# 06_ACCELEROMETER.net
KiCad netlist of a schematic drawn in Altium Designer
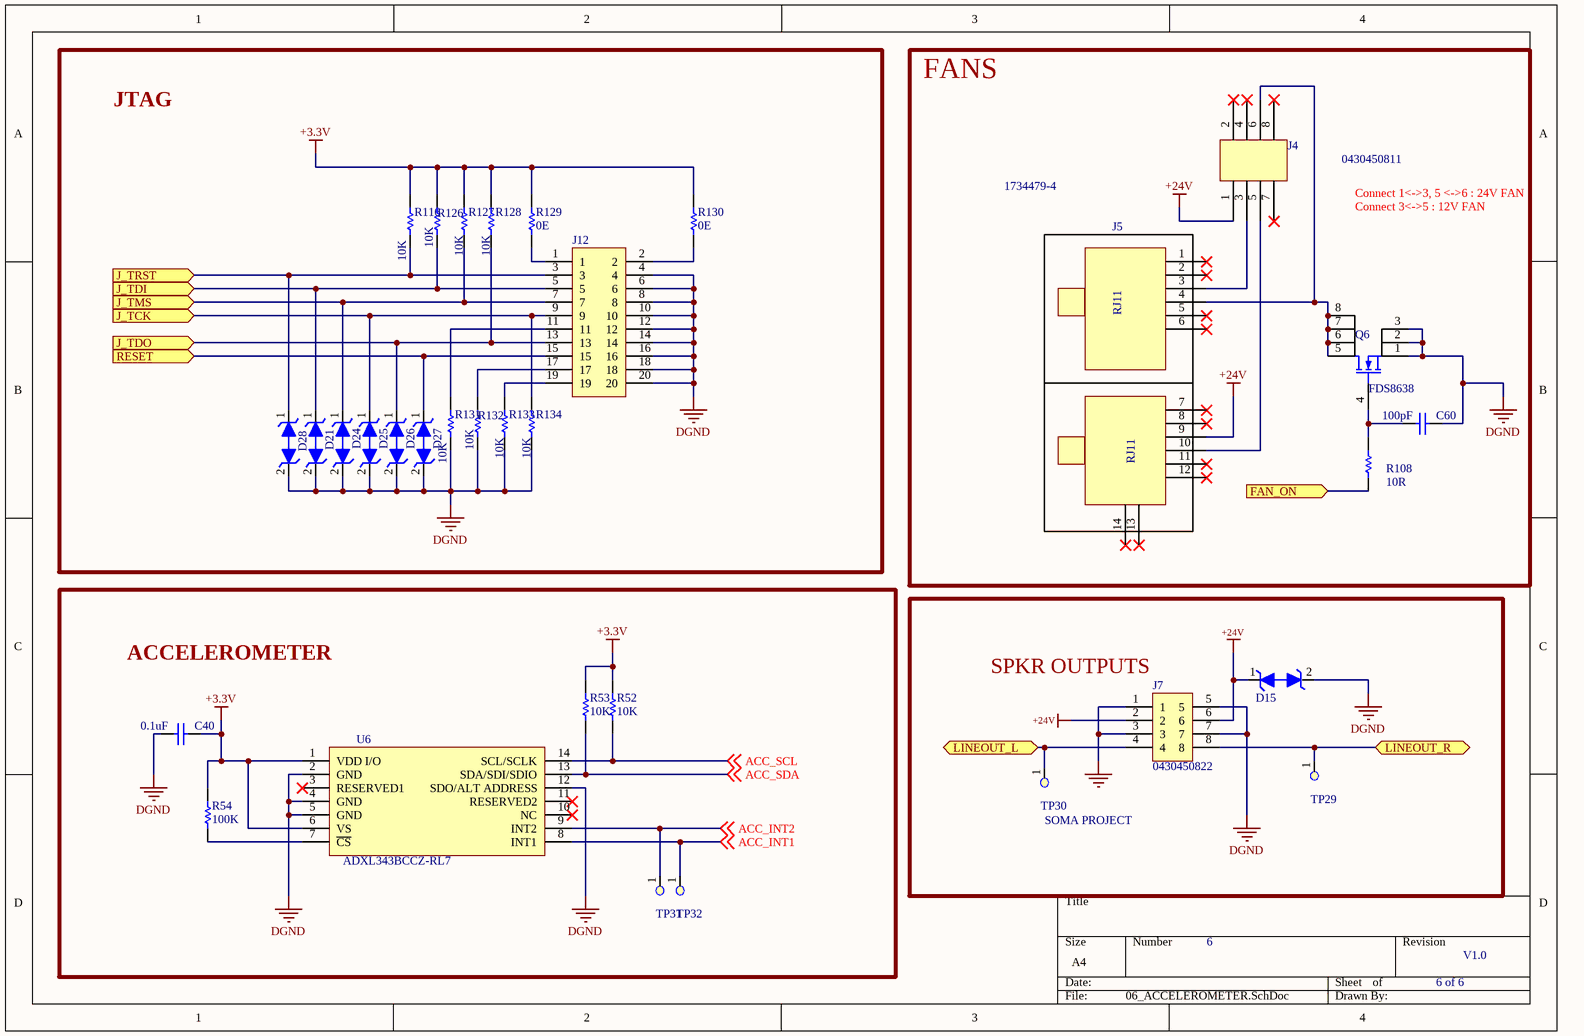
[diagram p0: 06_ACCELEROMETER.SchDoc]

(export (version "E")
  (design (tool "Eeschema 10.0.6"))
  (components
    (comp (ref "C40")
      (value "0.1uF")
      (footprint "C0402")
      (description "CAP CER 0.1UF 50V X7R 0402")
      (fields
        (field (name "MANUFACTURER") "AVX Corporation")
        (field (name "MANUFACTURER PART NUMBER") "04025C104KAT2A")
      )
      (libsource (lib "SOMA_15072021") (part "CAP CER 0.1UF 50V X7R 0402_1"))
    )
    (comp (ref "C60")
      (value "100pF")
      (footprint "C0402")
      (description "100 pF ±5% 50V Ceramic Capacitor C0G, NP0 0402 (1005 Metric)")
      (fields (field (name "TOLERANCE") "±5%") (field (name "MANUFACTURER") "KEMET"))
      (libsource (lib "SOMA_15072021") (part "CAP CER 100PF 50V C0G/NP0 0402"))
    )
    (comp (ref "D15")
      (value "TVS DIODE 24VWM 38.9VC SMC")
      (footprint "SOD8060X260N_BI")
      (description "38.9V Clamp 77.2A Ipp Tvs Diode Surface Mount DO-214AB (SMC)")
      (fields
        (field (name "MANUFACTURER") "Bourns Inc.")
        (field (name "MANUFACTURER PART NUMBER") "SMLJ24CA-Q")
      )
      (libsource (lib "SOMA_1") (part "TVS DIODE 24VWM 38.9VC SMC"))
    )
    (comp (ref "D21")
      (value "TVS DIODE 3.3V 11.5V SOD923")
      (footprint "SOD1006X40N_BI")
      (fields
        (field (name "MANUFACTURER PART NUMBER") "ESD9B3.3ST5G")
        (field (name "MANUFACTURER") "ON Semiconductor")
        (field (name "DISTRIBUTOR PART NUMBER") "ESD9B3.3ST5GOSTR-ND")
      )
      (libsource (lib "Daughtercard_Library") (part "Diode,ESD9B3.3ST5G"))
    )
    (comp (ref "D24")
      (value "TVS DIODE 3.3V 11.5V SOD923")
      (footprint "SOD1006X40N_BI")
      (fields
        (field (name "MANUFACTURER PART NUMBER") "ESD9B3.3ST5G")
        (field (name "MANUFACTURER") "ON Semiconductor")
        (field (name "DISTRIBUTOR PART NUMBER") "ESD9B3.3ST5GOSTR-ND")
      )
      (libsource (lib "Daughtercard_Library") (part "Diode,ESD9B3.3ST5G"))
    )
    (comp (ref "D25")
      (value "TVS DIODE 3.3V 11.5V SOD923")
      (footprint "SOD1006X40N_BI")
      (fields
        (field (name "MANUFACTURER PART NUMBER") "ESD9B3.3ST5G")
        (field (name "MANUFACTURER") "ON Semiconductor")
        (field (name "DISTRIBUTOR PART NUMBER") "ESD9B3.3ST5GOSTR-ND")
      )
      (libsource (lib "Daughtercard_Library") (part "Diode,ESD9B3.3ST5G"))
    )
    (comp (ref "D26")
      (value "TVS DIODE 3.3V 11.5V SOD923")
      (footprint "SOD1006X40N_BI")
      (fields
        (field (name "MANUFACTURER PART NUMBER") "ESD9B3.3ST5G")
        (field (name "MANUFACTURER") "ON Semiconductor")
        (field (name "DISTRIBUTOR PART NUMBER") "ESD9B3.3ST5GOSTR-ND")
      )
      (libsource (lib "Daughtercard_Library") (part "Diode,ESD9B3.3ST5G"))
    )
    (comp (ref "D27")
      (value "TVS DIODE 3.3V 11.5V SOD923")
      (footprint "SOD1006X40N_BI")
      (fields
        (field (name "MANUFACTURER PART NUMBER") "ESD9B3.3ST5G")
        (field (name "MANUFACTURER") "ON Semiconductor")
        (field (name "DISTRIBUTOR PART NUMBER") "ESD9B3.3ST5GOSTR-ND")
      )
      (libsource (lib "Daughtercard_Library") (part "Diode,ESD9B3.3ST5G"))
    )
    (comp (ref "D28")
      (value "TVS DIODE 3.3V 11.5V SOD923")
      (footprint "SOD1006X40N_BI")
      (fields
        (field (name "MANUFACTURER PART NUMBER") "ESD9B3.3ST5G")
        (field (name "MANUFACTURER") "ON Semiconductor")
        (field (name "DISTRIBUTOR PART NUMBER") "ESD9B3.3ST5GOSTR-ND")
      )
      (libsource (lib "Daughtercard_Library") (part "Diode,ESD9B3.3ST5G"))
    )
    (comp (ref "J4")
      (value "0430450811")
      (footprint "MOLEX_0430450811")
      (description "Connector Header Surface Mount, Right Angle 8 position 0.118\" (3.00mm)")
      (fields (field (name "DISTRIBUTOR PART NUMBER") "WM1834CT-ND") (field (name "MANUFACTURER") "Molex"))
      (libsource (lib "SOMA_15072021") (part "CONN HEADER SMD R/A 8POS 3MM"))
    )
    (comp (ref "J5")
      (value "1734479-4")
      (footprint "TE_17344794")
      (description "Jack Modular Connector 6p4c (RJ11, RJ14) 90° Angle (Right) Unshielded Cat3")
      (fields
        (field (name "DISTRIBUTOR PART NUMBER") "A119279-ND")
        (field (name "MANUFACTURER") "TE Connectivity AMP Connectors")
      )
      (libsource (lib "SOMA_15072021") (part "CONN MOD JACK 6P4C R/A UNSHLD"))
    )
    (comp (ref "J7")
      (value "0430450822")
      (footprint "MOLEX_430450822")
      (description "Connector Header Through Hole, Right Angle 8 position 0.118\" (3.00mm)")
      (fields (field (name "MANUFACTURER") "Molex") (field (name "DISTRIBUTOR PART NUMBER") "WM2681-ND"))
      (libsource (lib "SOMA_15072021") (part "CONN HEADER R/A 8POS 3MM"))
    )
    (comp (ref "J12")
      (value "SBH11-NBPC-D10-SM-BK")
      (footprint "SULLINS_SBH11-NBPC-D10-SM-BK")
      (fields
        (field (name "DISTRIBUTOR PART NUMBER") "S9188-ND")
        (field (name "MANUFACTURER") "Sullins")
        (field (name "TOLERANCE") "NA")
      )
      (libsource (lib "SOMA_15072021") (part "SBH11-NBPC-D10-SM-BK"))
    )
    (comp (ref "Q6")
      (value "FDS8638")
      (footprint "SOIC127P600X175-8N")
      (description "N-Channel 40 V 18A (Ta) 2.5W (Ta) Surface Mount 8-SOIC")
      (fields
        (field (name "DISTRIBUTOR PART NUMBER") "FDS8638CT-ND")
        (field (name "MANUFACTURER") "ON Semiconductor")
      )
      (libsource (lib "SOMA_15072021") (part "MOSFET N-CH 40V 18A 8SOIC"))
    )
    (comp (ref "R52")
      (value "10K")
      (footprint "R0402")
      (description "10 kOhms ±1% 0.1W, 1/10W Chip Resistor 0402 (1005 Metric) Automotive AEC-Q200 Thick Film")
      (fields
        (field (name "MANUFACTURER") "Panasonic Electronic Components")
        (field (name "DISTRIBUTOR PART NUMBER") "P10.0KLCT-ND")
      )
      (libsource (lib "Daughtercard_Library") (part "RES SMD 10K OHM 1% 1/10W 0402"))
    )
    (comp (ref "R53")
      (value "10K")
      (footprint "R0402")
      (description "10 kOhms ±1% 0.1W, 1/10W Chip Resistor 0402 (1005 Metric) Automotive AEC-Q200 Thick Film")
      (fields
        (field (name "MANUFACTURER") "Panasonic Electronic Components")
        (field (name "DISTRIBUTOR PART NUMBER") "P10.0KLCT-ND")
      )
      (libsource (lib "Daughtercard_Library") (part "RES SMD 10K OHM 1% 1/10W 0402"))
    )
    (comp (ref "R54")
      (value "100K")
      (footprint "R0402")
      (description "100 kOhms ±1% 0.1W, 1/10W Chip Resistor 0402 (1005 Metric) Automotive AEC-Q200 Thick Film")
      (fields
        (field (name "MANUFACTURER") "Panasonic Electronic Components")
        (field (name "MANUFACTURER PART NUMBER") "ERJ-2RKF1003X")
      )
      (libsource (lib "SOMA_15072021") (part "RES SMD 100K OHM 1% 1/10W 0402"))
    )
    (comp (ref "R108")
      (value "10R")
      (footprint "R0402")
      (description "10 Ohms ±5% 0.063W, 1/16W Chip Resistor 0402 (1005 Metric) Automotive AEC-Q200 Thick Film")
      (fields (field (name "TOLERANCE") "±5%") (field (name "MANUFACTURER") "Vishay Dale"))
      (libsource (lib "SOMA_15072021") (part "RES SMD 10 OHM 5% 1/16W 0402"))
    )
    (comp (ref "R116")
      (value "10K")
      (footprint "R0402")
      (description "10 kOhms ±1% 0.1W, 1/10W Chip Resistor 0402 (1005 Metric) Automotive AEC-Q200 Thick Film")
      (fields
        (field (name "MANUFACTURER") "Panasonic Electronic Components")
        (field (name "DISTRIBUTOR PART NUMBER") "P10.0KLCT-ND")
      )
      (libsource (lib "Daughtercard_Library") (part "RES SMD 10K OHM 1% 1/10W 0402"))
    )
    (comp (ref "R126")
      (value "10K")
      (footprint "R0402")
      (description "10 kOhms ±1% 0.1W, 1/10W Chip Resistor 0402 (1005 Metric) Automotive AEC-Q200 Thick Film")
      (fields
        (field (name "MANUFACTURER") "Panasonic Electronic Components")
        (field (name "DISTRIBUTOR PART NUMBER") "P10.0KLCT-ND")
      )
      (libsource (lib "Daughtercard_Library") (part "RES SMD 10K OHM 1% 1/10W 0402"))
    )
    (comp (ref "R127")
      (value "10K")
      (footprint "R0402")
      (description "10 kOhms ±1% 0.1W, 1/10W Chip Resistor 0402 (1005 Metric) Automotive AEC-Q200 Thick Film")
      (fields
        (field (name "MANUFACTURER") "Panasonic Electronic Components")
        (field (name "DISTRIBUTOR PART NUMBER") "P10.0KLCT-ND")
      )
      (libsource (lib "Daughtercard_Library") (part "RES SMD 10K OHM 1% 1/10W 0402"))
    )
    (comp (ref "R128")
      (value "10K")
      (footprint "R0402")
      (description "10 kOhms ±1% 0.1W, 1/10W Chip Resistor 0402 (1005 Metric) Automotive AEC-Q200 Thick Film")
      (fields
        (field (name "MANUFACTURER") "Panasonic Electronic Components")
        (field (name "DISTRIBUTOR PART NUMBER") "P10.0KLCT-ND")
      )
      (libsource (lib "Daughtercard_Library") (part "RES SMD 10K OHM 1% 1/10W 0402"))
    )
    (comp (ref "R129")
      (value "0E")
      (footprint "R0603")
      (description "RES SMD 0 OHM JUMPER 1/10W 0603")
      (fields
        (field (name "MANUFACTURER PART NUMBER") "RC0603JR-070RL")
        (field (name "MANUFACTURER") "Yageo")
      )
      (libsource (lib "PH_ORP_Sensor Board_Rev1") (part "RES SMD 0 OHM JUMPER 1/10W 0603"))
    )
    (comp (ref "R130")
      (value "0E")
      (footprint "R0603")
      (description "RES SMD 0 OHM JUMPER 1/10W 0603")
      (fields
        (field (name "MANUFACTURER PART NUMBER") "RC0603JR-070RL")
        (field (name "MANUFACTURER") "Yageo")
      )
      (libsource (lib "PH_ORP_Sensor Board_Rev1") (part "RES SMD 0 OHM JUMPER 1/10W 0603"))
    )
    (comp (ref "R131")
      (value "10K")
      (footprint "R0402")
      (description "10 kOhms ±1% 0.1W, 1/10W Chip Resistor 0402 (1005 Metric) Automotive AEC-Q200 Thick Film")
      (fields
        (field (name "MANUFACTURER") "Panasonic Electronic Components")
        (field (name "DISTRIBUTOR PART NUMBER") "P10.0KLCT-ND")
      )
      (libsource (lib "Daughtercard_Library") (part "RES SMD 10K OHM 1% 1/10W 0402"))
    )
    (comp (ref "R132")
      (value "10K")
      (footprint "R0402")
      (description "10 kOhms ±1% 0.1W, 1/10W Chip Resistor 0402 (1005 Metric) Automotive AEC-Q200 Thick Film")
      (fields
        (field (name "MANUFACTURER") "Panasonic Electronic Components")
        (field (name "DISTRIBUTOR PART NUMBER") "P10.0KLCT-ND")
      )
      (libsource (lib "Daughtercard_Library") (part "RES SMD 10K OHM 1% 1/10W 0402"))
    )
    (comp (ref "R133")
      (value "10K")
      (footprint "R0402")
      (description "10 kOhms ±1% 0.1W, 1/10W Chip Resistor 0402 (1005 Metric) Automotive AEC-Q200 Thick Film")
      (fields
        (field (name "MANUFACTURER") "Panasonic Electronic Components")
        (field (name "DISTRIBUTOR PART NUMBER") "P10.0KLCT-ND")
      )
      (libsource (lib "Daughtercard_Library") (part "RES SMD 10K OHM 1% 1/10W 0402"))
    )
    (comp (ref "R134")
      (value "10K")
      (footprint "R0402")
      (description "10 kOhms ±1% 0.1W, 1/10W Chip Resistor 0402 (1005 Metric) Automotive AEC-Q200 Thick Film")
      (fields
        (field (name "MANUFACTURER") "Panasonic Electronic Components")
        (field (name "DISTRIBUTOR PART NUMBER") "P10.0KLCT-ND")
      )
      (libsource (lib "Daughtercard_Library") (part "RES SMD 10K OHM 1% 1/10W 0402"))
    )
    (comp (ref "TP29")
      (value "Test Point,1.6mm Diameter,SMD")
      (footprint "TP_63C")
      (libsource (lib "SOMA_1") (part "Test Point,1.6mm Diameter,SMD"))
    )
    (comp (ref "TP30")
      (value "Test Point,1.6mm Diameter,SMD")
      (footprint "TP_63C")
      (libsource (lib "SOMA_1") (part "Test Point,1.6mm Diameter,SMD"))
    )
    (comp (ref "TP31")
      (value "Test Point,1.6mm Diameter,SMD")
      (footprint "TP_63C")
      (libsource (lib "SOMA_1") (part "Test Point,1.6mm Diameter,SMD"))
    )
    (comp (ref "TP32")
      (value "Test Point,1.6mm Diameter,SMD")
      (footprint "TP_63C")
      (libsource (lib "SOMA_1") (part "Test Point,1.6mm Diameter,SMD"))
    )
    (comp (ref "U6")
      (value "ACCEL 2-16G I2C/SPI 14LGA")
      (footprint "LGA14R80P8X6_500X300X100N")
      (description "Accelerometer X, Y, Z Axis ±2g, 4g, 8g, 16g 0.05Hz ~ 1.6kHz 14-LGA (3x5)")
      (fields
        (field (name "MANUFACTURER") "Analog Devices Inc.")
        (field (name "DISTRIBUTOR PART NUMBER") "ADXL343BCCZ-RL7CT-ND")
        (field (name "MANUFACTURER PART NUMBER") "ADXL343BCCZ-RL7")
      )
      (libsource (lib "SOMA_15072021") (part "ACCEL 2-16G I2C/SPI 14LGA"))
    )
  )
  (nets
    (net (code "1") (name "+3.3V") (class "Default")
      (node (ref "C40") (pin "1") (pinfunction "1_1") (pintype "passive"))
      (node (ref "R116") (pin "2") (pinfunction "2_2") (pintype "passive"))
      (node (ref "R126") (pin "2") (pinfunction "2_2") (pintype "passive"))
      (node (ref "R127") (pin "2") (pinfunction "2_2") (pintype "passive"))
      (node (ref "R128") (pin "2") (pinfunction "2_2") (pintype "passive"))
      (node (ref "R129") (pin "2") (pinfunction "2_2") (pintype "passive"))
      (node (ref "R130") (pin "2") (pinfunction "2_2") (pintype "passive"))
      (node (ref "R52") (pin "2") (pinfunction "2_2") (pintype "passive"))
      (node (ref "R53") (pin "2") (pinfunction "2_2") (pintype "passive"))
      (node (ref "R54") (pin "2") (pinfunction "2_2") (pintype "passive"))
      (node (ref "U6") (pin "1") (pinfunction "VDD_I/O_1") (pintype "passive"))
      (node (ref "U6") (pin "6") (pinfunction "VS_6") (pintype "passive"))
    )
    (net (code "2") (name "+24V") (class "Default")
      (node (ref "D15") (pin "1") (pinfunction "K_1") (pintype "passive"))
      (node (ref "J4") (pin "1") (pintype "passive"))
      (node (ref "J5") (pin "9") (pinfunction "9_9") (pintype "passive"))
      (node (ref "J7") (pin "2") (pinfunction "2_2") (pintype "passive"))
      (node (ref "J7") (pin "6") (pinfunction "6_6") (pintype "passive"))
    )
    (net (code "5") (name "/FAN_ON") (class "Default")
      (node (ref "R108") (pin "1") (pinfunction "1_1") (pintype "passive"))
    )
    (net (code "6") (name "/J_TCK") (class "Default")
      (node (ref "D25") (pin "1") (pinfunction "K_1") (pintype "passive"))
      (node (ref "J12") (pin "9") (pinfunction "9_9") (pintype "passive"))
      (node (ref "R134") (pin "2") (pinfunction "2_2") (pintype "passive"))
    )
    (net (code "7") (name "/J_TDI") (class "Default")
      (node (ref "D21") (pin "1") (pinfunction "K_1") (pintype "passive"))
      (node (ref "J12") (pin "5") (pinfunction "5_5") (pintype "passive"))
      (node (ref "R126") (pin "1") (pinfunction "1_1") (pintype "passive"))
    )
    (net (code "8") (name "/J_TDO") (class "Default")
      (node (ref "D26") (pin "1") (pinfunction "K_1") (pintype "passive"))
      (node (ref "J12") (pin "13") (pinfunction "13_13") (pintype "passive"))
      (node (ref "R128") (pin "1") (pinfunction "1_1") (pintype "passive"))
    )
    (net (code "9") (name "/J_TMS") (class "Default")
      (node (ref "D24") (pin "1") (pinfunction "K_1") (pintype "passive"))
      (node (ref "J12") (pin "7") (pinfunction "7_7") (pintype "passive"))
      (node (ref "R127") (pin "1") (pinfunction "1_1") (pintype "passive"))
    )
    (net (code "10") (name "/J_TRST") (class "Default")
      (node (ref "D28") (pin "1") (pinfunction "K_1") (pintype "passive"))
      (node (ref "J12") (pin "3") (pinfunction "3_3") (pintype "passive"))
      (node (ref "R116") (pin "1") (pinfunction "1_1") (pintype "passive"))
    )
    (net (code "11") (name "/LINEOUT_L") (class "Default")
      (node (ref "J7") (pin "4") (pinfunction "4_4") (pintype "passive"))
      (node (ref "TP30") (pin "1") (pinfunction "0_1") (pintype "passive"))
    )
    (net (code "12") (name "/LINEOUT_R") (class "Default")
      (node (ref "J7") (pin "8") (pinfunction "8_8") (pintype "passive"))
      (node (ref "TP29") (pin "1") (pinfunction "0_1") (pintype "passive"))
    )
    (net (code "13") (name "/RESET") (class "Default")
      (node (ref "D27") (pin "1") (pinfunction "K_1") (pintype "passive"))
      (node (ref "J12") (pin "15") (pinfunction "15_15") (pintype "passive"))
    )
    (net (code "14") (name "ACC_INT1") (class "Default")
      (node (ref "TP32") (pin "1") (pinfunction "0_1") (pintype "passive"))
      (node (ref "U6") (pin "8") (pinfunction "INT1_8") (pintype "passive"))
    )
    (net (code "15") (name "ACC_INT2") (class "Default")
      (node (ref "TP31") (pin "1") (pinfunction "0_1") (pintype "passive"))
      (node (ref "U6") (pin "9") (pinfunction "INT2_9") (pintype "passive"))
    )
    (net (code "16") (name "ACC_SCL") (class "Default")
      (node (ref "R52") (pin "1") (pinfunction "1_1") (pintype "passive"))
      (node (ref "U6") (pin "14") (pinfunction "SCL/SCLK_14") (pintype "passive"))
    )
    (net (code "17") (name "ACC_SDA") (class "Default")
      (node (ref "R53") (pin "1") (pinfunction "1_1") (pintype "passive"))
      (node (ref "U6") (pin "13") (pinfunction "SDA/SDI/SDIO_13") (pintype "passive"))
    )
    (net (code "18") (name "DGND") (class "Default")
      (node (ref "C40") (pin "2") (pinfunction "2_2") (pintype "passive"))
      (node (ref "C60") (pin "1") (pinfunction "1_1") (pintype "passive"))
      (node (ref "D15") (pin "2") (pinfunction "A_2") (pintype "passive"))
      (node (ref "D21") (pin "2") (pinfunction "A_2") (pintype "passive"))
      (node (ref "D24") (pin "2") (pinfunction "A_2") (pintype "passive"))
      (node (ref "D25") (pin "2") (pinfunction "A_2") (pintype "passive"))
      (node (ref "D26") (pin "2") (pinfunction "A_2") (pintype "passive"))
      (node (ref "D27") (pin "2") (pinfunction "A_2") (pintype "passive"))
      (node (ref "D28") (pin "2") (pinfunction "A_2") (pintype "passive"))
      (node (ref "J12") (pin "10") (pinfunction "10_10") (pintype "passive"))
      (node (ref "J12") (pin "12") (pinfunction "12_12") (pintype "passive"))
      (node (ref "J12") (pin "14") (pinfunction "14_14") (pintype "passive"))
      (node (ref "J12") (pin "16") (pinfunction "16_16") (pintype "passive"))
      (node (ref "J12") (pin "18") (pinfunction "18_18") (pintype "passive"))
      (node (ref "J12") (pin "20") (pinfunction "20_20") (pintype "passive"))
      (node (ref "J12") (pin "4") (pinfunction "4_4") (pintype "passive"))
      (node (ref "J12") (pin "6") (pinfunction "6_6") (pintype "passive"))
      (node (ref "J12") (pin "8") (pinfunction "8_8") (pintype "passive"))
      (node (ref "J7") (pin "5") (pinfunction "5_5") (pintype "passive"))
      (node (ref "J7") (pin "7") (pinfunction "7_7") (pintype "passive"))
      (node (ref "Q6") (pin "1") (pinfunction "1_1") (pintype "passive"))
      (node (ref "Q6") (pin "2") (pinfunction "2_2") (pintype "passive"))
      (node (ref "Q6") (pin "3") (pinfunction "3_3") (pintype "passive"))
      (node (ref "R131") (pin "1") (pinfunction "1_1") (pintype "passive"))
      (node (ref "R132") (pin "1") (pinfunction "1_1") (pintype "passive"))
      (node (ref "R133") (pin "1") (pinfunction "1_1") (pintype "passive"))
      (node (ref "R134") (pin "1") (pinfunction "1_1") (pintype "passive"))
      (node (ref "U6") (pin "12") (pinfunction "SDO/ALT_ADDRESS_12") (pintype "passive"))
      (node (ref "U6") (pin "2") (pinfunction "GND_2") (pintype "passive"))
      (node (ref "U6") (pin "4") (pinfunction "GND_4") (pintype "passive"))
      (node (ref "U6") (pin "5") (pinfunction "GND_5") (pintype "passive"))
    )
    (net (code "19") (name "GND") (class "Default")
      (node (ref "J7") (pin "1") (pinfunction "1_1") (pintype "passive"))
      (node (ref "J7") (pin "3") (pinfunction "3_3") (pintype "passive"))
    )
    (net (code "20") (name "Net-(C60-Pad2)") (class "Default")
      (node (ref "C60") (pin "2") (pinfunction "2_2") (pintype "passive"))
      (node (ref "Q6") (pin "4") (pinfunction "4_4") (pintype "passive"))
      (node (ref "R108") (pin "2") (pinfunction "2_2") (pintype "passive"))
    )
    (net (code "21") (name "Net-(J4-Pad3)") (class "Default")
      (node (ref "J4") (pin "3") (pintype "passive"))
      (node (ref "J5") (pin "3") (pinfunction "3_3") (pintype "passive"))
    )
    (net (code "22") (name "Net-(J4-Pad5)") (class "Default")
      (node (ref "J4") (pin "5") (pintype "passive"))
      (node (ref "J5") (pin "10") (pinfunction "10_10") (pintype "passive"))
    )
    (net (code "23") (name "Net-(J4-Pad6)") (class "Default")
      (node (ref "J4") (pin "6") (pintype "passive"))
      (node (ref "J5") (pin "4") (pinfunction "4_4") (pintype "passive"))
      (node (ref "Q6") (pin "5") (pinfunction "5_5") (pintype "passive"))
      (node (ref "Q6") (pin "6") (pinfunction "6_6") (pintype "passive"))
      (node (ref "Q6") (pin "7") (pinfunction "7_7") (pintype "passive"))
      (node (ref "Q6") (pin "8") (pinfunction "8_8") (pintype "passive"))
    )
    (net (code "24") (name "Net-(J12-Pad1)") (class "Default")
      (node (ref "J12") (pin "1") (pinfunction "1_1") (pintype "passive"))
      (node (ref "R129") (pin "1") (pinfunction "1_1") (pintype "passive"))
    )
    (net (code "25") (name "Net-(J12-Pad2)") (class "Default")
      (node (ref "J12") (pin "2") (pinfunction "2_2") (pintype "passive"))
      (node (ref "R130") (pin "1") (pinfunction "1_1") (pintype "passive"))
    )
    (net (code "26") (name "Net-(J12-Pad11)") (class "Default")
      (node (ref "J12") (pin "11") (pinfunction "11_11") (pintype "passive"))
      (node (ref "R131") (pin "2") (pinfunction "2_2") (pintype "passive"))
    )
    (net (code "27") (name "Net-(J12-Pad17)") (class "Default")
      (node (ref "J12") (pin "17") (pinfunction "17_17") (pintype "passive"))
      (node (ref "R132") (pin "2") (pinfunction "2_2") (pintype "passive"))
    )
    (net (code "28") (name "Net-(J12-Pad19)") (class "Default")
      (node (ref "J12") (pin "19") (pinfunction "19_19") (pintype "passive"))
      (node (ref "R133") (pin "2") (pinfunction "2_2") (pintype "passive"))
    )
    (net (code "29") (name "Net-(U6-~{CS})") (class "Default")
      (node (ref "R54") (pin "1") (pinfunction "1_1") (pintype "passive"))
      (node (ref "U6") (pin "7") (pinfunction "~{CS}_7") (pintype "passive"))
    )
    (net (code "30") (name "unconnected-(J4-Pad2)") (class "Default")
      (node (ref "J4") (pin "2") (pintype "passive+no_connect"))
    )
    (net (code "31") (name "unconnected-(J4-Pad4)") (class "Default")
      (node (ref "J4") (pin "4") (pintype "passive+no_connect"))
    )
    (net (code "32") (name "unconnected-(J4-Pad7)") (class "Default")
      (node (ref "J4") (pin "7") (pinfunction "7_7") (pintype "passive+no_connect"))
    )
    (net (code "33") (name "unconnected-(J4-Pad8)") (class "Default")
      (node (ref "J4") (pin "8") (pinfunction "8_8") (pintype "passive+no_connect"))
    )
    (net (code "34") (name "unconnected-(J5-Pad1)") (class "Default")
      (node (ref "J5") (pin "1") (pinfunction "1_1") (pintype "passive+no_connect"))
    )
    (net (code "35") (name "unconnected-(J5-Pad2)") (class "Default")
      (node (ref "J5") (pin "2") (pinfunction "2_2") (pintype "passive+no_connect"))
    )
    (net (code "36") (name "unconnected-(J5-Pad5)") (class "Default")
      (node (ref "J5") (pin "5") (pinfunction "5_5") (pintype "passive+no_connect"))
    )
    (net (code "37") (name "unconnected-(J5-Pad6)") (class "Default")
      (node (ref "J5") (pin "6") (pinfunction "6_6") (pintype "passive+no_connect"))
    )
    (net (code "38") (name "unconnected-(J5-Pad7)") (class "Default")
      (node (ref "J5") (pin "7") (pinfunction "7_7") (pintype "passive+no_connect"))
    )
    (net (code "39") (name "unconnected-(J5-Pad8)") (class "Default")
      (node (ref "J5") (pin "8") (pinfunction "8_8") (pintype "passive+no_connect"))
    )
    (net (code "40") (name "unconnected-(J5-Pad11)") (class "Default")
      (node (ref "J5") (pin "11") (pinfunction "11_11") (pintype "passive+no_connect"))
    )
    (net (code "41") (name "unconnected-(J5-Pad12)") (class "Default")
      (node (ref "J5") (pin "12") (pinfunction "12_12") (pintype "passive+no_connect"))
    )
    (net (code "42") (name "unconnected-(J5-Pad13)") (class "Default")
      (node (ref "J5") (pin "13") (pinfunction "13_13") (pintype "passive+no_connect"))
    )
    (net (code "43") (name "unconnected-(J5-Pad14)") (class "Default")
      (node (ref "J5") (pin "14") (pinfunction "14_14") (pintype "passive+no_connect"))
    )
    (net (code "44") (name "unconnected-(U6-NC-Pad10)") (class "Default")
      (node (ref "U6") (pin "10") (pinfunction "NC_10") (pintype "passive+no_connect"))
    )
    (net (code "45") (name "unconnected-(U6-RESERVED1-Pad3)") (class "Default")
      (node (ref "U6") (pin "3") (pinfunction "RESERVED1_3") (pintype "passive+no_connect"))
    )
    (net (code "46") (name "unconnected-(U6-RESERVED2-Pad11)") (class "Default")
      (node (ref "U6") (pin "11") (pinfunction "RESERVED2_11") (pintype "passive+no_connect"))
    )
  )
)
